# ssr-breakout.net
KiCad netlist of a schematic drawn in EAGLE
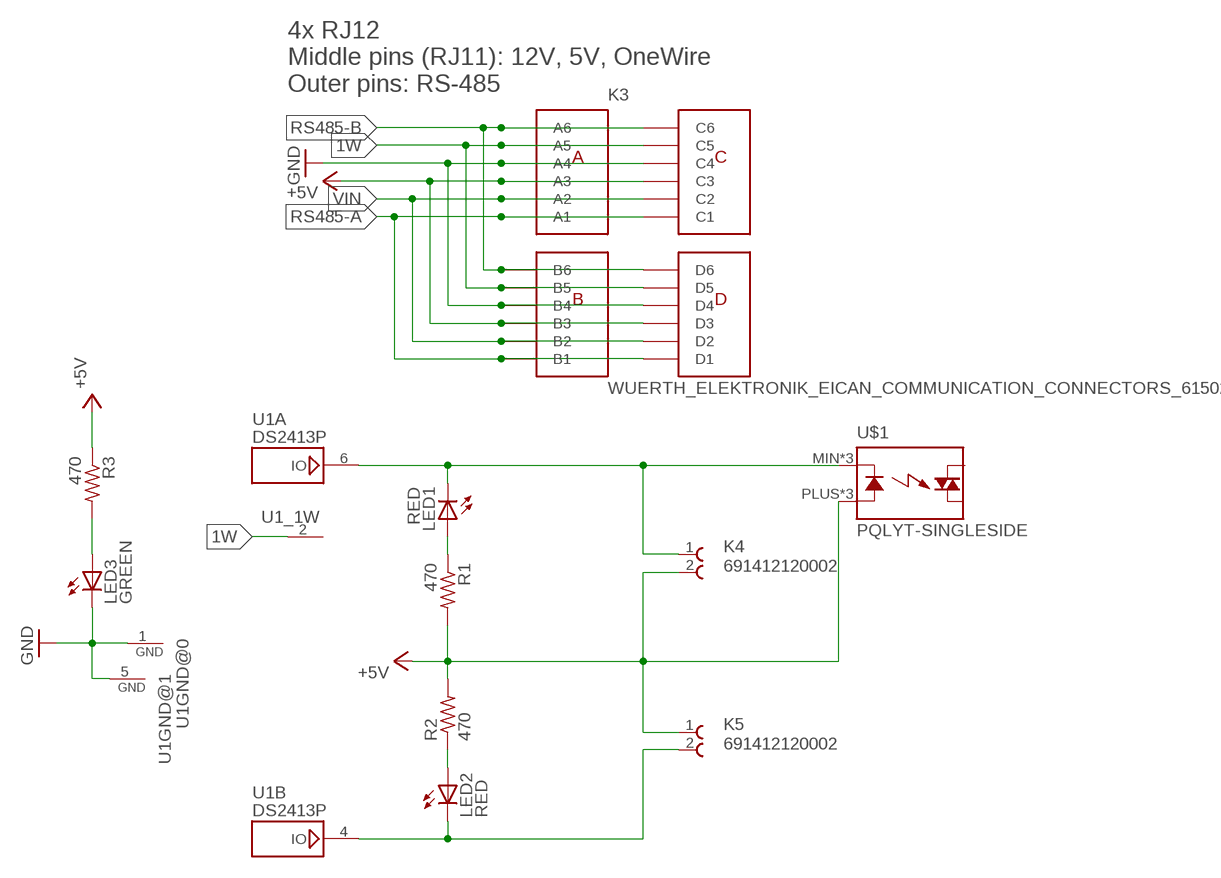
[diagram p0: schematic, sheet 1]

(export (version "E")
  (design (tool "Eeschema 10.0.6"))
  (components
    (comp (ref "K3")
      (value "WUERTH_ELEKTRONIK_EICAN_COMMUNICATION_CONNECTORS_615024143921")
      (footprint "eagle-import:WUERTH_ELEKTRONIK_EICAN_COMMUNICATION_CONNECTORS_615024143921")
      (libsource (lib "eagle-import") (part "WUERTH_ELEKTRONIK_EICAN_COMMUNICATION_CONNECTORS_615024143921"))
    )
    (comp (ref "K4")
      (value "691412120002")
      (footprint "eagle-import:691412120002")
      (libsource (lib "eagle-import") (part "691412120002"))
    )
    (comp (ref "K5")
      (value "691412120002")
      (footprint "eagle-import:691412120002")
      (libsource (lib "eagle-import") (part "691412120002"))
    )
    (comp (ref "LED1")
      (value "RED")
      (footprint "eagle-import:SPARKFUN-LED_LED-1206")
      (libsource (lib "eagle-import") (part "SPARKFUN-LED_LED-BLUE1206"))
    )
    (comp (ref "LED2")
      (value "RED")
      (footprint "eagle-import:SPARKFUN-LED_LED-1206")
      (libsource (lib "eagle-import") (part "SPARKFUN-LED_LED-BLUE1206"))
    )
    (comp (ref "LED3")
      (value "GREEN")
      (footprint "eagle-import:SPARKFUN-LED_LED-1206")
      (libsource (lib "eagle-import") (part "SPARKFUN-LED_LED-BLUE1206"))
    )
    (comp (ref "R1")
      (value "470")
      (footprint "eagle-import:R0805")
      (libsource (lib "eagle-import") (part "R-US_R0805"))
    )
    (comp (ref "R2")
      (value "470")
      (footprint "eagle-import:R0805")
      (libsource (lib "eagle-import") (part "R-US_R0805"))
    )
    (comp (ref "R3")
      (value "470")
      (footprint "eagle-import:R0805")
      (libsource (lib "eagle-import") (part "R-US_R0805"))
    )
    (comp (ref "U$1")
      (value "PQLYT-SINGLESIDE")
      (footprint "eagle-import:PQLYT-PADS-ONLY")
      (libsource (lib "eagle-import") (part "PQLYT-SINGLESIDE"))
    )
    (comp (ref "U1")
      (value "DS2413P")
      (footprint "eagle-import:TSOC6")
      (libsource (lib "eagle-import") (part "DS2413P"))
    )
  )
  (nets
    (net (code "1") (name "+5V") (class "Default")
      (node (ref "K3") (pin "A3") (pinfunction "A3_A3") (pintype "passive"))
      (node (ref "K3") (pin "B3") (pinfunction "B3_B3") (pintype "passive"))
      (node (ref "K3") (pin "C3") (pinfunction "C3_C3") (pintype "passive"))
      (node (ref "K3") (pin "D3") (pinfunction "D3_D3") (pintype "passive"))
      (node (ref "K4") (pin "2") (pinfunction "2_2") (pintype "passive"))
      (node (ref "K5") (pin "1") (pinfunction "1_1") (pintype "passive"))
      (node (ref "R1") (pin "2") (pinfunction "2_2") (pintype "passive"))
      (node (ref "R2") (pin "2") (pinfunction "2_2") (pintype "passive"))
      (node (ref "R3") (pin "1") (pinfunction "1_1") (pintype "passive"))
      (node (ref "U$1") (pin "PLUS") (pinfunction "A_PLUS") (pintype "passive"))
      (node (ref "U$1") (pin "PLUSBOTTOM") (pinfunction "A_PLUSBOTTOM") (pintype "passive"))
      (node (ref "U$1") (pin "PLUSTOP") (pinfunction "A_PLUSTOP") (pintype "passive"))
    )
    (net (code "2") (name "1W") (class "Default")
      (node (ref "K3") (pin "A5") (pinfunction "A5_A5") (pintype "passive"))
      (node (ref "K3") (pin "B5") (pinfunction "B5_B5") (pintype "passive"))
      (node (ref "K3") (pin "C5") (pinfunction "C5_C5") (pintype "passive"))
      (node (ref "K3") (pin "D5") (pinfunction "D5_D5") (pintype "passive"))
      (node (ref "U1") (pin "2") (pinfunction "1W_2") (pintype "power_in"))
    )
    (net (code "3") (name "GND") (class "Default")
      (node (ref "K3") (pin "A4") (pinfunction "A4_A4") (pintype "passive"))
      (node (ref "K3") (pin "B4") (pinfunction "B4_B4") (pintype "passive"))
      (node (ref "K3") (pin "C4") (pinfunction "C4_C4") (pintype "passive"))
      (node (ref "K3") (pin "D4") (pinfunction "D4_D4") (pintype "passive"))
      (node (ref "LED3") (pin "C") (pinfunction "C_C") (pintype "passive"))
      (node (ref "U1") (pin "1") (pinfunction "GND_1") (pintype "power_in"))
      (node (ref "U1") (pin "5") (pinfunction "GND_5") (pintype "power_in"))
    )
    (net (code "4") (name "Net-(LED1-PadA)") (class "Default")
      (node (ref "LED1") (pin "A") (pinfunction "A_A") (pintype "passive"))
      (node (ref "R1") (pin "1") (pinfunction "1_1") (pintype "passive"))
    )
    (net (code "5") (name "Net-(LED2-PadA)") (class "Default")
      (node (ref "LED2") (pin "A") (pinfunction "A_A") (pintype "passive"))
      (node (ref "R2") (pin "1") (pinfunction "1_1") (pintype "passive"))
    )
    (net (code "6") (name "Net-(LED3-PadA)") (class "Default")
      (node (ref "LED3") (pin "A") (pinfunction "A_A") (pintype "passive"))
      (node (ref "R3") (pin "2") (pinfunction "2_2") (pintype "passive"))
    )
    (net (code "7") (name "Net-(U1A-IO)") (class "Default")
      (node (ref "K4") (pin "1") (pinfunction "1_1") (pintype "passive"))
      (node (ref "LED1") (pin "C") (pinfunction "C_C") (pintype "passive"))
      (node (ref "U$1") (pin "MIN") (pinfunction "K_MIN") (pintype "passive"))
      (node (ref "U$1") (pin "MINBOTTOM") (pinfunction "K_MINBOTTOM") (pintype "passive"))
      (node (ref "U$1") (pin "MINTOP") (pinfunction "K_MINTOP") (pintype "passive"))
      (node (ref "U1") (pin "6") (pinfunction "IO_6") (pintype "open_collector"))
    )
    (net (code "8") (name "Net-(U1B-IO)") (class "Default")
      (node (ref "K5") (pin "2") (pinfunction "2_2") (pintype "passive"))
      (node (ref "LED2") (pin "C") (pinfunction "C_C") (pintype "passive"))
      (node (ref "U1") (pin "4") (pinfunction "IO_4") (pintype "open_collector"))
    )
    (net (code "9") (name "RS485-A") (class "Default")
      (node (ref "K3") (pin "A1") (pinfunction "A1_A1") (pintype "passive"))
      (node (ref "K3") (pin "B1") (pinfunction "B1_B1") (pintype "passive"))
      (node (ref "K3") (pin "C1") (pinfunction "C1_C1") (pintype "passive"))
      (node (ref "K3") (pin "D1") (pinfunction "D1_D1") (pintype "passive"))
    )
    (net (code "10") (name "RS485-B") (class "Default")
      (node (ref "K3") (pin "A6") (pinfunction "A6_A6") (pintype "passive"))
      (node (ref "K3") (pin "B6") (pinfunction "B6_B6") (pintype "passive"))
      (node (ref "K3") (pin "C6") (pinfunction "C6_C6") (pintype "passive"))
      (node (ref "K3") (pin "D6") (pinfunction "D6_D6") (pintype "passive"))
    )
    (net (code "11") (name "VIN") (class "Default")
      (node (ref "K3") (pin "A2") (pinfunction "A2_A2") (pintype "passive"))
      (node (ref "K3") (pin "B2") (pinfunction "B2_B2") (pintype "passive"))
      (node (ref "K3") (pin "C2") (pinfunction "C2_C2") (pintype "passive"))
      (node (ref "K3") (pin "D2") (pinfunction "D2_D2") (pintype "passive"))
    )
  )
)
